# MP9928_converter.net
KiCad netlist of a schematic drawn in Altium Designer
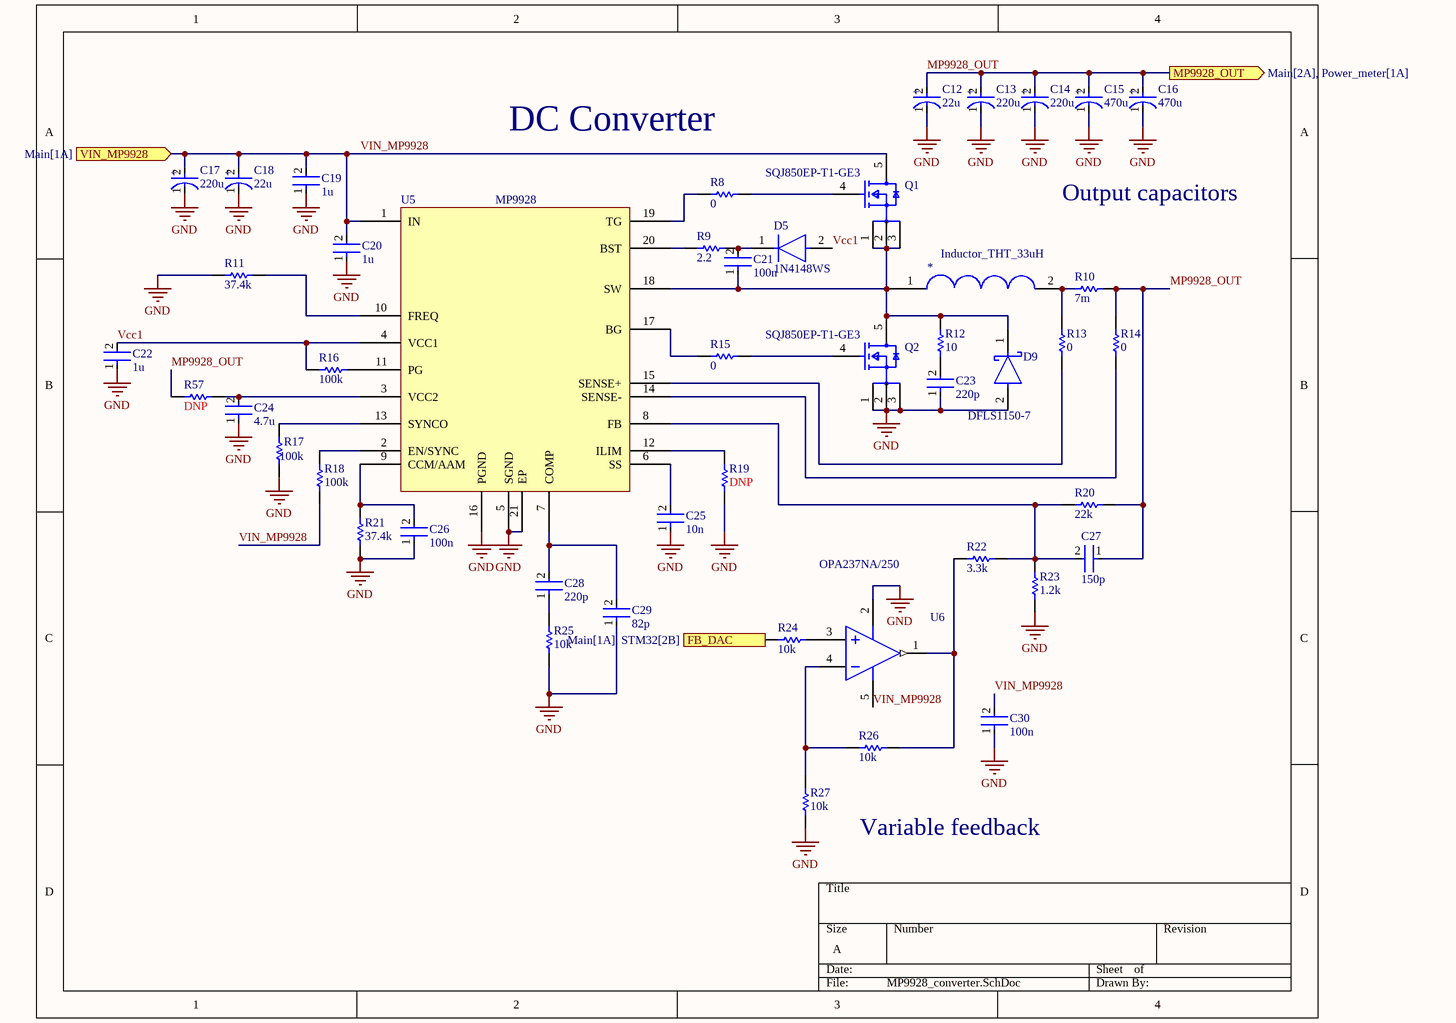
[diagram p0: MP9928_converter.SchDoc]

(export (version "E")
  (design (tool "Eeschema 10.0.6"))
  (components
    (comp (ref "*")
      (value "Inductor_THT_33uH")
      (footprint "Inductor_THT")
      (libsource (lib "Schlib1") (part "Inductor_THT_33uH"))
    )
    (comp (ref "C12")
      (value "22u")
      (footprint "FP-FKG-MFG")
      (description "CAP ALUM 220UF 20% 50V SMD")
      (fields (field (name "TOLERANCE") "20%") (field (name "MANUFACTURER") "Panasonic"))
      (libsource (lib "Altium Content Vault") (part "203bc49f2ac43e59fd269a8c329ed05"))
    )
    (comp (ref "C13")
      (value "220u")
      (footprint "FP-FKG-MFG")
      (description "CAP ALUM 220UF 20% 50V SMD")
      (fields (field (name "TOLERANCE") "20%") (field (name "MANUFACTURER") "Panasonic"))
      (libsource (lib "Altium Content Vault") (part "203bc49f2ac43e59fd269a8c329ed05"))
    )
    (comp (ref "C14")
      (value "220u")
      (footprint "FP-FKG-MFG")
      (description "CAP ALUM 220UF 20% 50V SMD")
      (fields (field (name "TOLERANCE") "20%") (field (name "MANUFACTURER") "Panasonic"))
      (libsource (lib "Altium Content Vault") (part "203bc49f2ac43e59fd269a8c329ed05"))
    )
    (comp (ref "C15")
      (value "470u")
      (footprint "FP-FKJ16-MFG")
      (description "CAP ALUM 470UF 20% 50V SMD")
      (fields (field (name "VOLTAGE") "50V") (field (name "TOLERANCE") "20%"))
      (libsource (lib "Altium Content Vault") (part "a00bbbee19879c290e62620ae7e47b1"))
    )
    (comp (ref "C16")
      (value "470u")
      (footprint "FP-FKJ16-MFG")
      (description "CAP ALUM 470UF 20% 50V SMD")
      (fields (field (name "VOLTAGE") "50V") (field (name "TOLERANCE") "20%"))
      (libsource (lib "Altium Content Vault") (part "a00bbbee19879c290e62620ae7e47b1"))
    )
    (comp (ref "C17")
      (value "220u")
      (footprint "FP-FKG-MFG")
      (description "CAP ALUM 220UF 20% 50V SMD")
      (fields (field (name "TOLERANCE") "20%") (field (name "MANUFACTURER") "Panasonic"))
      (libsource (lib "Altium Content Vault") (part "203bc49f2ac43e59fd269a8c329ed05"))
    )
    (comp (ref "C18")
      (value "22u")
      (footprint "FP-FKG-MFG")
      (description "CAP ALUM 220UF 20% 50V SMD")
      (fields (field (name "TOLERANCE") "20%") (field (name "MANUFACTURER") "Panasonic"))
      (libsource (lib "Altium Content Vault") (part "203bc49f2ac43e59fd269a8c329ed05"))
    )
    (comp (ref "C19")
      (value "1u")
      (footprint "FP-0805-L_2_01_0_2-W_1_25-IPC_B")
      (description "General Purpose Ceramic Capacitor, 0805, 100nF, 10%, X7R, 15%, 100V")
      (fields (field (name "VOLTAGE") "100V") (field (name "TOLERANCE") "10%"))
      (libsource (lib "Altium Content Vault") (part "b4654b650e69147ec39a6b967a45e02"))
    )
    (comp (ref "C20")
      (value "1u")
      (footprint "FP-0805-L_2_01_0_2-W_1_25-IPC_B")
      (description "General Purpose Ceramic Capacitor, 0805, 100nF, 10%, X7R, 15%, 100V")
      (fields (field (name "VOLTAGE") "100V") (field (name "TOLERANCE") "10%"))
      (libsource (lib "Altium Content Vault") (part "b4654b650e69147ec39a6b967a45e02"))
    )
    (comp (ref "C21")
      (value "100n")
      (footprint "FP-0805-L_2_01_0_2-W_1_25-IPC_B")
      (description "General Purpose Ceramic Capacitor, 0805, 100nF, 10%, X7R, 15%, 100V")
      (fields (field (name "VOLTAGE") "100V") (field (name "TOLERANCE") "10%"))
      (libsource (lib "Altium Content Vault") (part "b4654b650e69147ec39a6b967a45e02"))
    )
    (comp (ref "C22")
      (value "1u")
      (footprint "FP-0805-L_2_01_0_2-W_1_25-IPC_B")
      (description "General Purpose Ceramic Capacitor, 0805, 100nF, 10%, X7R, 15%, 100V")
      (fields (field (name "VOLTAGE") "100V") (field (name "TOLERANCE") "10%"))
      (libsource (lib "Altium Content Vault") (part "b4654b650e69147ec39a6b967a45e02"))
    )
    (comp (ref "C23")
      (value "220p")
      (footprint "FP-0805-L_2_01_0_2-W_1_25-IPC_B")
      (description "General Purpose Ceramic Capacitor, 0805, 100nF, 10%, X7R, 15%, 100V")
      (fields (field (name "VOLTAGE") "100V") (field (name "TOLERANCE") "10%"))
      (libsource (lib "Altium Content Vault") (part "b4654b650e69147ec39a6b967a45e02"))
    )
    (comp (ref "C24")
      (value "4.7u")
      (footprint "FP-0805-L_2_01_0_2-W_1_25-IPC_B")
      (description "General Purpose Ceramic Capacitor, 0805, 100nF, 10%, X7R, 15%, 100V")
      (fields (field (name "VOLTAGE") "100V") (field (name "TOLERANCE") "10%"))
      (libsource (lib "Altium Content Vault") (part "b4654b650e69147ec39a6b967a45e02"))
    )
    (comp (ref "C25")
      (value "10n")
      (footprint "FP-0805-L_2_01_0_2-W_1_25-IPC_B")
      (description "General Purpose Ceramic Capacitor, 0805, 100nF, 10%, X7R, 15%, 100V")
      (fields (field (name "VOLTAGE") "100V") (field (name "TOLERANCE") "10%"))
      (libsource (lib "Altium Content Vault") (part "b4654b650e69147ec39a6b967a45e02"))
    )
    (comp (ref "C26")
      (value "100n")
      (footprint "FP-0805-L_2_01_0_2-W_1_25-IPC_B")
      (description "General Purpose Ceramic Capacitor, 0805, 100nF, 10%, X7R, 15%, 100V")
      (fields (field (name "VOLTAGE") "100V") (field (name "TOLERANCE") "10%"))
      (libsource (lib "Altium Content Vault") (part "b4654b650e69147ec39a6b967a45e02"))
    )
    (comp (ref "C27")
      (value "150p")
      (footprint "FP-0805-L_2_01_0_2-W_1_25-IPC_B")
      (description "General Purpose Ceramic Capacitor, 0805, 100nF, 10%, X7R, 15%, 100V")
      (fields (field (name "VOLTAGE") "100V") (field (name "TOLERANCE") "10%"))
      (libsource (lib "Altium Content Vault") (part "b4654b650e69147ec39a6b967a45e02"))
    )
    (comp (ref "C28")
      (value "220p")
      (footprint "FP-0805-L_2_01_0_2-W_1_25-IPC_B")
      (description "General Purpose Ceramic Capacitor, 0805, 100nF, 10%, X7R, 15%, 100V")
      (fields (field (name "VOLTAGE") "100V") (field (name "TOLERANCE") "10%"))
      (libsource (lib "Altium Content Vault") (part "b4654b650e69147ec39a6b967a45e02"))
    )
    (comp (ref "C29")
      (value "82p")
      (footprint "FP-0805-L_2_01_0_2-W_1_25-IPC_B")
      (description "General Purpose Ceramic Capacitor, 0805, 100nF, 10%, X7R, 15%, 100V")
      (fields (field (name "VOLTAGE") "100V") (field (name "TOLERANCE") "10%"))
      (libsource (lib "Altium Content Vault") (part "b4654b650e69147ec39a6b967a45e02"))
    )
    (comp (ref "C30")
      (value "100n")
      (footprint "FP-0805-L_2_01_0_2-W_1_25-IPC_B")
      (description "General Purpose Ceramic Capacitor, 0805, 100nF, 10%, X7R, 15%, 100V")
      (fields (field (name "VOLTAGE") "100V") (field (name "TOLERANCE") "10%"))
      (libsource (lib "Altium Content Vault") (part "b4654b650e69147ec39a6b967a45e02"))
    )
    (comp (ref "D5")
      (value "1N4148WS")
      (footprint "FP-477AB-IPC_C")
      (description "DIODE GEN PURP 75V 150MA SOD323F")
      (libsource (lib "Altium Content Vault") (part "d7152d700b627762746794eb795d46e"))
    )
    (comp (ref "D9")
      (value "DFLS1150-7")
      (footprint "FP-PowerDI123-MFG")
      (description "DIODE SCHOTTKY 150V POWERDI123")
      (fields
        (field (name "OCTOPART") "https://octopart.com/dfls1150-7-diodes+inc.-328567")
        (field (name "MANUFACTURER") "Diodes Inc.")
      )
      (libsource (lib "Altium Content Vault") (part "1d6ec82d83fb6aee721767c19dac4b9"))
    )
    (comp (ref "Q1")
      (value "SQJ850EP-T1-GE3")
      (footprint "FP-T16-0221-SINGLE-MFG")
      (description "MOSFET N-CH 60V 24A")
      (fields
        (field (name "OCTOPART") "https://octopart.com/sqj850ep-t1_ge3-vishay-63675376")
        (field (name "MANUFACTURER") "Vishay")
      )
      (libsource (lib "Altium Content Vault") (part "8b2635d381df023462af6787da82583"))
    )
    (comp (ref "Q2")
      (value "SQJ850EP-T1-GE3")
      (footprint "FP-T16-0221-SINGLE-MFG")
      (description "MOSFET N-CH 60V 24A")
      (fields
        (field (name "OCTOPART") "https://octopart.com/sqj850ep-t1_ge3-vishay-63675376")
        (field (name "MANUFACTURER") "Vishay")
      )
      (libsource (lib "Altium Content Vault") (part "8b2635d381df023462af6787da82583"))
    )
    (comp (ref "R8")
      (value "0")
      (footprint "RESC2013X50X30LL20T20")
      (fields (field (name "MANUFACTURER") "Vishay Dale") (field (name "PART NUMBER") "CRCW08050000Z0EA"))
      (libsource (lib "Altium Content Vault") (part "RES"))
    )
    (comp (ref "R9")
      (value "2.2")
      (footprint "RESC2013X50X30LL20T20")
      (fields (field (name "MANUFACTURER") "Vishay Dale") (field (name "PART NUMBER") "CRCW08050000Z0EA"))
      (libsource (lib "Altium Content Vault") (part "RES"))
    )
    (comp (ref "R10")
      (value "7m")
      (footprint "RESC3216X70X50NL05T20")
      (description "Shunt resistor")
      (fields (field (name "PART NUMBER") "ERJ8BSFR10V") (field (name "MANUFACTURER") "Panasonic"))
      (libsource (lib "Altium Content Vault") (part "RES"))
    )
    (comp (ref "R11")
      (value "37.4k")
      (footprint "RESC2013X50X30LL20T20")
      (fields (field (name "MANUFACTURER") "Vishay Dale") (field (name "PART NUMBER") "CRCW08050000Z0EA"))
      (libsource (lib "Altium Content Vault") (part "RES"))
    )
    (comp (ref "R12")
      (value "10")
      (footprint "RESC2013X50X30LL20T20")
      (fields (field (name "MANUFACTURER") "Vishay Dale") (field (name "PART NUMBER") "CRCW08050000Z0EA"))
      (libsource (lib "Altium Content Vault") (part "RES"))
    )
    (comp (ref "R13")
      (value "0")
      (footprint "RESC2013X50X30LL20T20")
      (fields (field (name "MANUFACTURER") "Vishay Dale") (field (name "PART NUMBER") "CRCW08050000Z0EA"))
      (libsource (lib "Altium Content Vault") (part "RES"))
    )
    (comp (ref "R14")
      (value "0")
      (footprint "RESC2013X50X30LL20T20")
      (fields (field (name "MANUFACTURER") "Vishay Dale") (field (name "PART NUMBER") "CRCW08050000Z0EA"))
      (libsource (lib "Altium Content Vault") (part "RES"))
    )
    (comp (ref "R15")
      (value "0")
      (footprint "RESC2013X50X30LL20T20")
      (fields (field (name "MANUFACTURER") "Vishay Dale") (field (name "PART NUMBER") "CRCW08050000Z0EA"))
      (libsource (lib "Altium Content Vault") (part "RES"))
    )
    (comp (ref "R16")
      (value "100k")
      (footprint "RESC2013X50X30LL20T20")
      (fields (field (name "MANUFACTURER") "Vishay Dale") (field (name "PART NUMBER") "CRCW08050000Z0EA"))
      (libsource (lib "Altium Content Vault") (part "RES"))
    )
    (comp (ref "R17")
      (value "100k")
      (footprint "RESC2013X50X30LL20T20")
      (fields (field (name "MANUFACTURER") "Vishay Dale") (field (name "PART NUMBER") "CRCW08050000Z0EA"))
      (libsource (lib "Altium Content Vault") (part "RES"))
    )
    (comp (ref "R18")
      (value "100k")
      (footprint "RESC2013X50X30LL20T20")
      (fields (field (name "MANUFACTURER") "Vishay Dale") (field (name "PART NUMBER") "CRCW08050000Z0EA"))
      (libsource (lib "Altium Content Vault") (part "RES"))
    )
    (comp (ref "R19")
      (value "DNP")
      (footprint "RESC2013X50X30LL20T20")
      (fields (field (name "MANUFACTURER") "Vishay Dale") (field (name "PART NUMBER") "CRCW08050000Z0EA"))
      (libsource (lib "Altium Content Vault") (part "RES"))
    )
    (comp (ref "R20")
      (value "22k")
      (footprint "RESC2013X50X30LL20T20")
      (fields (field (name "MANUFACTURER") "Vishay Dale") (field (name "PART NUMBER") "CRCW08050000Z0EA"))
      (libsource (lib "Altium Content Vault") (part "RES"))
    )
    (comp (ref "R21")
      (value "37.4k")
      (footprint "RESC2013X50X30LL20T20")
      (fields (field (name "MANUFACTURER") "Vishay Dale") (field (name "PART NUMBER") "CRCW08050000Z0EA"))
      (libsource (lib "Altium Content Vault") (part "RES"))
    )
    (comp (ref "R22")
      (value "3.3k")
      (footprint "RESC2013X50X30LL20T20")
      (fields (field (name "MANUFACTURER") "Vishay Dale") (field (name "PART NUMBER") "CRCW08050000Z0EA"))
      (libsource (lib "Altium Content Vault") (part "RES"))
    )
    (comp (ref "R23")
      (value "1.2k")
      (footprint "RESC2013X50X30LL20T20")
      (fields (field (name "MANUFACTURER") "Vishay Dale") (field (name "PART NUMBER") "CRCW08050000Z0EA"))
      (libsource (lib "Altium Content Vault") (part "RES"))
    )
    (comp (ref "R24")
      (value "10k")
      (footprint "RESC2013X50X30LL20T20")
      (fields (field (name "MANUFACTURER") "Vishay Dale") (field (name "PART NUMBER") "CRCW08050000Z0EA"))
      (libsource (lib "Altium Content Vault") (part "RES"))
    )
    (comp (ref "R25")
      (value "10k")
      (footprint "RESC2013X50X30LL20T20")
      (fields (field (name "MANUFACTURER") "Vishay Dale") (field (name "PART NUMBER") "CRCW08050000Z0EA"))
      (libsource (lib "Altium Content Vault") (part "RES"))
    )
    (comp (ref "R26")
      (value "10k")
      (footprint "RESC2013X50X30LL20T20")
      (fields (field (name "MANUFACTURER") "Vishay Dale") (field (name "PART NUMBER") "CRCW08050000Z0EA"))
      (libsource (lib "Altium Content Vault") (part "RES"))
    )
    (comp (ref "R27")
      (value "10k")
      (footprint "RESC2013X50X30LL20T20")
      (fields (field (name "MANUFACTURER") "Vishay Dale") (field (name "PART NUMBER") "CRCW08050000Z0EA"))
      (libsource (lib "Altium Content Vault") (part "RES"))
    )
    (comp (ref "R57")
      (value "DNP")
      (footprint "RESC2013X50X30LL20T20")
      (fields (field (name "MANUFACTURER") "Vishay Dale") (field (name "PART NUMBER") "CRCW08050000Z0EA"))
      (libsource (lib "Altium Content Vault") (part "RES"))
    )
    (comp (ref "U5")
      (value "MP9928")
      (footprint "SOP65P640X110-21N")
      (libsource (lib "Schlib1") (part "MP9928"))
    )
    (comp (ref "U6")
      (value "OPA237NA/250")
      (footprint "DBV0005A_N")
      (fields (field (name "MANUFACTURER") "Texas Instruments"))
      (libsource (lib "Altium Content Vault") (part "TI-OPA_SM7XXXX-DBV5"))
    )
  )
  (nets
    (net (code "1") (name "/FB_DAC") (class "Default")
      (node (ref "R24") (pin "1") (pinfunction "1_1") (pintype "passive"))
    )
    (net (code "2") (name "/MP9928_OUT") (class "Default")
      (node (ref "C12") (pin "2") (pinfunction "A_2") (pintype "passive"))
      (node (ref "C13") (pin "2") (pinfunction "A_2") (pintype "passive"))
      (node (ref "C14") (pin "2") (pinfunction "A_2") (pintype "passive"))
      (node (ref "C15") (pin "2") (pinfunction "A_2") (pintype "passive"))
      (node (ref "C16") (pin "2") (pinfunction "A_2") (pintype "passive"))
      (node (ref "C27") (pin "1") (pinfunction "1_1") (pintype "passive"))
      (node (ref "R10") (pin "2") (pinfunction "2_2") (pintype "passive"))
      (node (ref "R14") (pin "1") (pinfunction "1_1") (pintype "passive"))
      (node (ref "R20") (pin "2") (pinfunction "2_2") (pintype "passive"))
      (node (ref "R57") (pin "1") (pinfunction "1_1") (pintype "passive"))
    )
    (net (code "3") (name "/VIN_MP9928") (class "Default")
      (node (ref "C17") (pin "2") (pinfunction "A_2") (pintype "passive"))
      (node (ref "C18") (pin "2") (pinfunction "A_2") (pintype "passive"))
      (node (ref "C19") (pin "2") (pinfunction "2_2") (pintype "passive"))
      (node (ref "C20") (pin "2") (pinfunction "2_2") (pintype "passive"))
      (node (ref "C30") (pin "2") (pinfunction "2_2") (pintype "passive"))
      (node (ref "Q1") (pin "5") (pinfunction "D_5") (pintype "passive"))
      (node (ref "R18") (pin "2") (pinfunction "2_2") (pintype "passive"))
      (node (ref "U5") (pin "1") (pinfunction "IN_1") (pintype "passive"))
      (node (ref "U6") (pin "5") (pinfunction "V+_5") (pintype "passive"))
    )
    (net (code "4") (name "/Vcc1") (class "Default")
      (node (ref "C22") (pin "2") (pinfunction "2_2") (pintype "passive"))
      (node (ref "D5") (pin "2") (pinfunction "A_2") (pintype "passive"))
      (node (ref "R16") (pin "2") (pinfunction "2_2") (pintype "passive"))
      (node (ref "U5") (pin "4") (pinfunction "VCC1_4") (pintype "passive"))
    )
    (net (code "5") (name "GND") (class "Default")
      (node (ref "C12") (pin "1") (pinfunction "C_1") (pintype "passive"))
      (node (ref "C13") (pin "1") (pinfunction "C_1") (pintype "passive"))
      (node (ref "C14") (pin "1") (pinfunction "C_1") (pintype "passive"))
      (node (ref "C15") (pin "1") (pinfunction "C_1") (pintype "passive"))
      (node (ref "C16") (pin "1") (pinfunction "C_1") (pintype "passive"))
      (node (ref "C17") (pin "1") (pinfunction "C_1") (pintype "passive"))
      (node (ref "C18") (pin "1") (pinfunction "C_1") (pintype "passive"))
      (node (ref "C19") (pin "1") (pinfunction "1_1") (pintype "passive"))
      (node (ref "C20") (pin "1") (pinfunction "1_1") (pintype "passive"))
      (node (ref "C22") (pin "1") (pinfunction "1_1") (pintype "passive"))
      (node (ref "C23") (pin "1") (pinfunction "1_1") (pintype "passive"))
      (node (ref "C24") (pin "1") (pinfunction "1_1") (pintype "passive"))
      (node (ref "C25") (pin "1") (pinfunction "1_1") (pintype "passive"))
      (node (ref "C26") (pin "1") (pinfunction "1_1") (pintype "passive"))
      (node (ref "C29") (pin "1") (pinfunction "1_1") (pintype "passive"))
      (node (ref "C30") (pin "1") (pinfunction "1_1") (pintype "passive"))
      (node (ref "D9") (pin "2") (pinfunction "A_2") (pintype "passive"))
      (node (ref "Q2") (pin "1") (pinfunction "S_1") (pintype "passive"))
      (node (ref "Q2") (pin "2") (pinfunction "S_2") (pintype "passive"))
      (node (ref "Q2") (pin "3") (pinfunction "S_3") (pintype "passive"))
      (node (ref "R11") (pin "1") (pinfunction "1_1") (pintype "passive"))
      (node (ref "R17") (pin "2") (pinfunction "2_2") (pintype "passive"))
      (node (ref "R19") (pin "2") (pinfunction "2_2") (pintype "passive"))
      (node (ref "R21") (pin "2") (pinfunction "2_2") (pintype "passive"))
      (node (ref "R23") (pin "2") (pinfunction "2_2") (pintype "passive"))
      (node (ref "R25") (pin "2") (pinfunction "2_2") (pintype "passive"))
      (node (ref "R27") (pin "2") (pinfunction "2_2") (pintype "passive"))
      (node (ref "U5") (pin "16") (pinfunction "PGND_16") (pintype "power_in"))
      (node (ref "U5") (pin "21") (pinfunction "EP_21") (pintype "passive"))
      (node (ref "U5") (pin "5") (pinfunction "SGND_5") (pintype "power_in"))
      (node (ref "U6") (pin "2") (pinfunction "V-_2") (pintype "power_in"))
    )
    (net (code "6") (name "Net-(*-Pad2)") (class "Default")
      (node (ref "*") (pin "2") (pintype "passive"))
      (node (ref "R10") (pin "1") (pinfunction "1_1") (pintype "passive"))
      (node (ref "R13") (pin "1") (pinfunction "1_1") (pintype "passive"))
    )
    (net (code "7") (name "Net-(C23-Pad2)") (class "Default")
      (node (ref "C23") (pin "2") (pinfunction "2_2") (pintype "passive"))
      (node (ref "R12") (pin "2") (pinfunction "2_2") (pintype "passive"))
    )
    (net (code "8") (name "Net-(C28-Pad1)") (class "Default")
      (node (ref "C28") (pin "1") (pinfunction "1_1") (pintype "passive"))
      (node (ref "R25") (pin "1") (pinfunction "1_1") (pintype "passive"))
    )
    (net (code "9") (name "Net-(D5-C)") (class "Default")
      (node (ref "C21") (pin "2") (pinfunction "2_2") (pintype "passive"))
      (node (ref "D5") (pin "1") (pinfunction "C_1") (pintype "passive"))
      (node (ref "R9") (pin "1") (pinfunction "1_1") (pintype "passive"))
    )
    (net (code "10") (name "Net-(D9-C)") (class "Default")
      (node (ref "*") (pin "1") (pinfunction "1_1") (pintype "passive"))
      (node (ref "C21") (pin "1") (pinfunction "1_1") (pintype "passive"))
      (node (ref "D9") (pin "1") (pinfunction "C_1") (pintype "passive"))
      (node (ref "Q1") (pin "1") (pinfunction "S_1") (pintype "passive"))
      (node (ref "Q1") (pin "2") (pinfunction "S_2") (pintype "passive"))
      (node (ref "Q1") (pin "3") (pinfunction "S_3") (pintype "passive"))
      (node (ref "Q2") (pin "5") (pinfunction "D_5") (pintype "passive"))
      (node (ref "R12") (pin "1") (pinfunction "1_1") (pintype "passive"))
      (node (ref "U5") (pin "18") (pinfunction "SW_18") (pintype "passive"))
    )
    (net (code "11") (name "Net-(Q1-G)") (class "Default")
      (node (ref "Q1") (pin "4") (pinfunction "G_4") (pintype "passive"))
      (node (ref "R8") (pin "1") (pinfunction "1_1") (pintype "passive"))
    )
    (net (code "12") (name "Net-(Q2-G)") (class "Default")
      (node (ref "Q2") (pin "4") (pinfunction "G_4") (pintype "passive"))
      (node (ref "R15") (pin "1") (pinfunction "1_1") (pintype "passive"))
    )
    (net (code "13") (name "Net-(U5-BG)") (class "Default")
      (node (ref "R15") (pin "2") (pinfunction "2_2") (pintype "passive"))
      (node (ref "U5") (pin "17") (pinfunction "BG_17") (pintype "passive"))
    )
    (net (code "14") (name "Net-(U5-BST)") (class "Default")
      (node (ref "R9") (pin "2") (pinfunction "2_2") (pintype "passive"))
      (node (ref "U5") (pin "20") (pinfunction "BST_20") (pintype "passive"))
    )
    (net (code "15") (name "Net-(U5-CCM{slash}AAM)") (class "Default")
      (node (ref "C26") (pin "2") (pinfunction "2_2") (pintype "passive"))
      (node (ref "R21") (pin "1") (pinfunction "1_1") (pintype "passive"))
      (node (ref "U5") (pin "9") (pinfunction "CCM/AAM_9") (pintype "passive"))
    )
    (net (code "16") (name "Net-(U5-COMP)") (class "Default")
      (node (ref "C28") (pin "2") (pinfunction "2_2") (pintype "passive"))
      (node (ref "C29") (pin "2") (pinfunction "2_2") (pintype "passive"))
      (node (ref "U5") (pin "7") (pinfunction "COMP_7") (pintype "passive"))
    )
    (net (code "17") (name "Net-(U5-EN{slash}SYNC)") (class "Default")
      (node (ref "R18") (pin "1") (pinfunction "1_1") (pintype "passive"))
      (node (ref "U5") (pin "2") (pinfunction "EN/SYNC_2") (pintype "passive"))
    )
    (net (code "18") (name "Net-(U5-FB)") (class "Default")
      (node (ref "C27") (pin "2") (pinfunction "2_2") (pintype "passive"))
      (node (ref "R20") (pin "1") (pinfunction "1_1") (pintype "passive"))
      (node (ref "R22") (pin "1") (pinfunction "1_1") (pintype "passive"))
      (node (ref "R23") (pin "1") (pinfunction "1_1") (pintype "passive"))
      (node (ref "U5") (pin "8") (pinfunction "FB_8") (pintype "passive"))
    )
    (net (code "19") (name "Net-(U5-FREQ)") (class "Default")
      (node (ref "R11") (pin "2") (pinfunction "2_2") (pintype "passive"))
      (node (ref "U5") (pin "10") (pinfunction "FREQ_10") (pintype "passive"))
    )
    (net (code "20") (name "Net-(U5-ILIM)") (class "Default")
      (node (ref "R19") (pin "1") (pinfunction "1_1") (pintype "passive"))
      (node (ref "U5") (pin "12") (pinfunction "ILIM_12") (pintype "passive"))
    )
    (net (code "21") (name "Net-(U5-PG)") (class "Default")
      (node (ref "R16") (pin "1") (pinfunction "1_1") (pintype "passive"))
      (node (ref "U5") (pin "11") (pinfunction "PG_11") (pintype "passive"))
    )
    (net (code "22") (name "Net-(U5-SENSE+)") (class "Default")
      (node (ref "R13") (pin "2") (pinfunction "2_2") (pintype "passive"))
      (node (ref "U5") (pin "15") (pinfunction "SENSE+_15") (pintype "passive"))
    )
    (net (code "23") (name "Net-(U5-SENSE-)") (class "Default")
      (node (ref "R14") (pin "2") (pinfunction "2_2") (pintype "passive"))
      (node (ref "U5") (pin "14") (pinfunction "SENSE-_14") (pintype "passive"))
    )
    (net (code "24") (name "Net-(U5-SS)") (class "Default")
      (node (ref "C25") (pin "2") (pinfunction "2_2") (pintype "passive"))
      (node (ref "U5") (pin "6") (pinfunction "SS_6") (pintype "passive"))
    )
    (net (code "25") (name "Net-(U5-SYNCO)") (class "Default")
      (node (ref "R17") (pin "1") (pinfunction "1_1") (pintype "passive"))
      (node (ref "U5") (pin "13") (pinfunction "SYNCO_13") (pintype "passive"))
    )
    (net (code "26") (name "Net-(U5-TG)") (class "Default")
      (node (ref "R8") (pin "2") (pinfunction "2_2") (pintype "passive"))
      (node (ref "U5") (pin "19") (pinfunction "TG_19") (pintype "passive"))
    )
    (net (code "27") (name "Net-(U5-VCC2)") (class "Default")
      (node (ref "C24") (pin "2") (pinfunction "2_2") (pintype "passive"))
      (node (ref "R57") (pin "2") (pinfunction "2_2") (pintype "passive"))
      (node (ref "U5") (pin "3") (pinfunction "VCC2_3") (pintype "passive"))
    )
    (net (code "28") (name "Net-(U6-IN+)") (class "Default")
      (node (ref "R24") (pin "2") (pinfunction "2_2") (pintype "passive"))
      (node (ref "U6") (pin "3") (pinfunction "IN+_3") (pintype "passive"))
    )
    (net (code "29") (name "Net-(U6-IN-)") (class "Default")
      (node (ref "R26") (pin "1") (pinfunction "1_1") (pintype "passive"))
      (node (ref "R27") (pin "1") (pinfunction "1_1") (pintype "passive"))
      (node (ref "U6") (pin "4") (pinfunction "IN-_4") (pintype "passive"))
    )
    (net (code "30") (name "Net-(U6-OUT)") (class "Default")
      (node (ref "R22") (pin "2") (pinfunction "2_2") (pintype "passive"))
      (node (ref "R26") (pin "2") (pinfunction "2_2") (pintype "passive"))
      (node (ref "U6") (pin "1") (pinfunction "OUT_1") (pintype "output"))
    )
  )
)
